# STM32F4_TFT-Proto_Adapter_FSMC.net
KiCad netlist of a schematic drawn in EAGLE
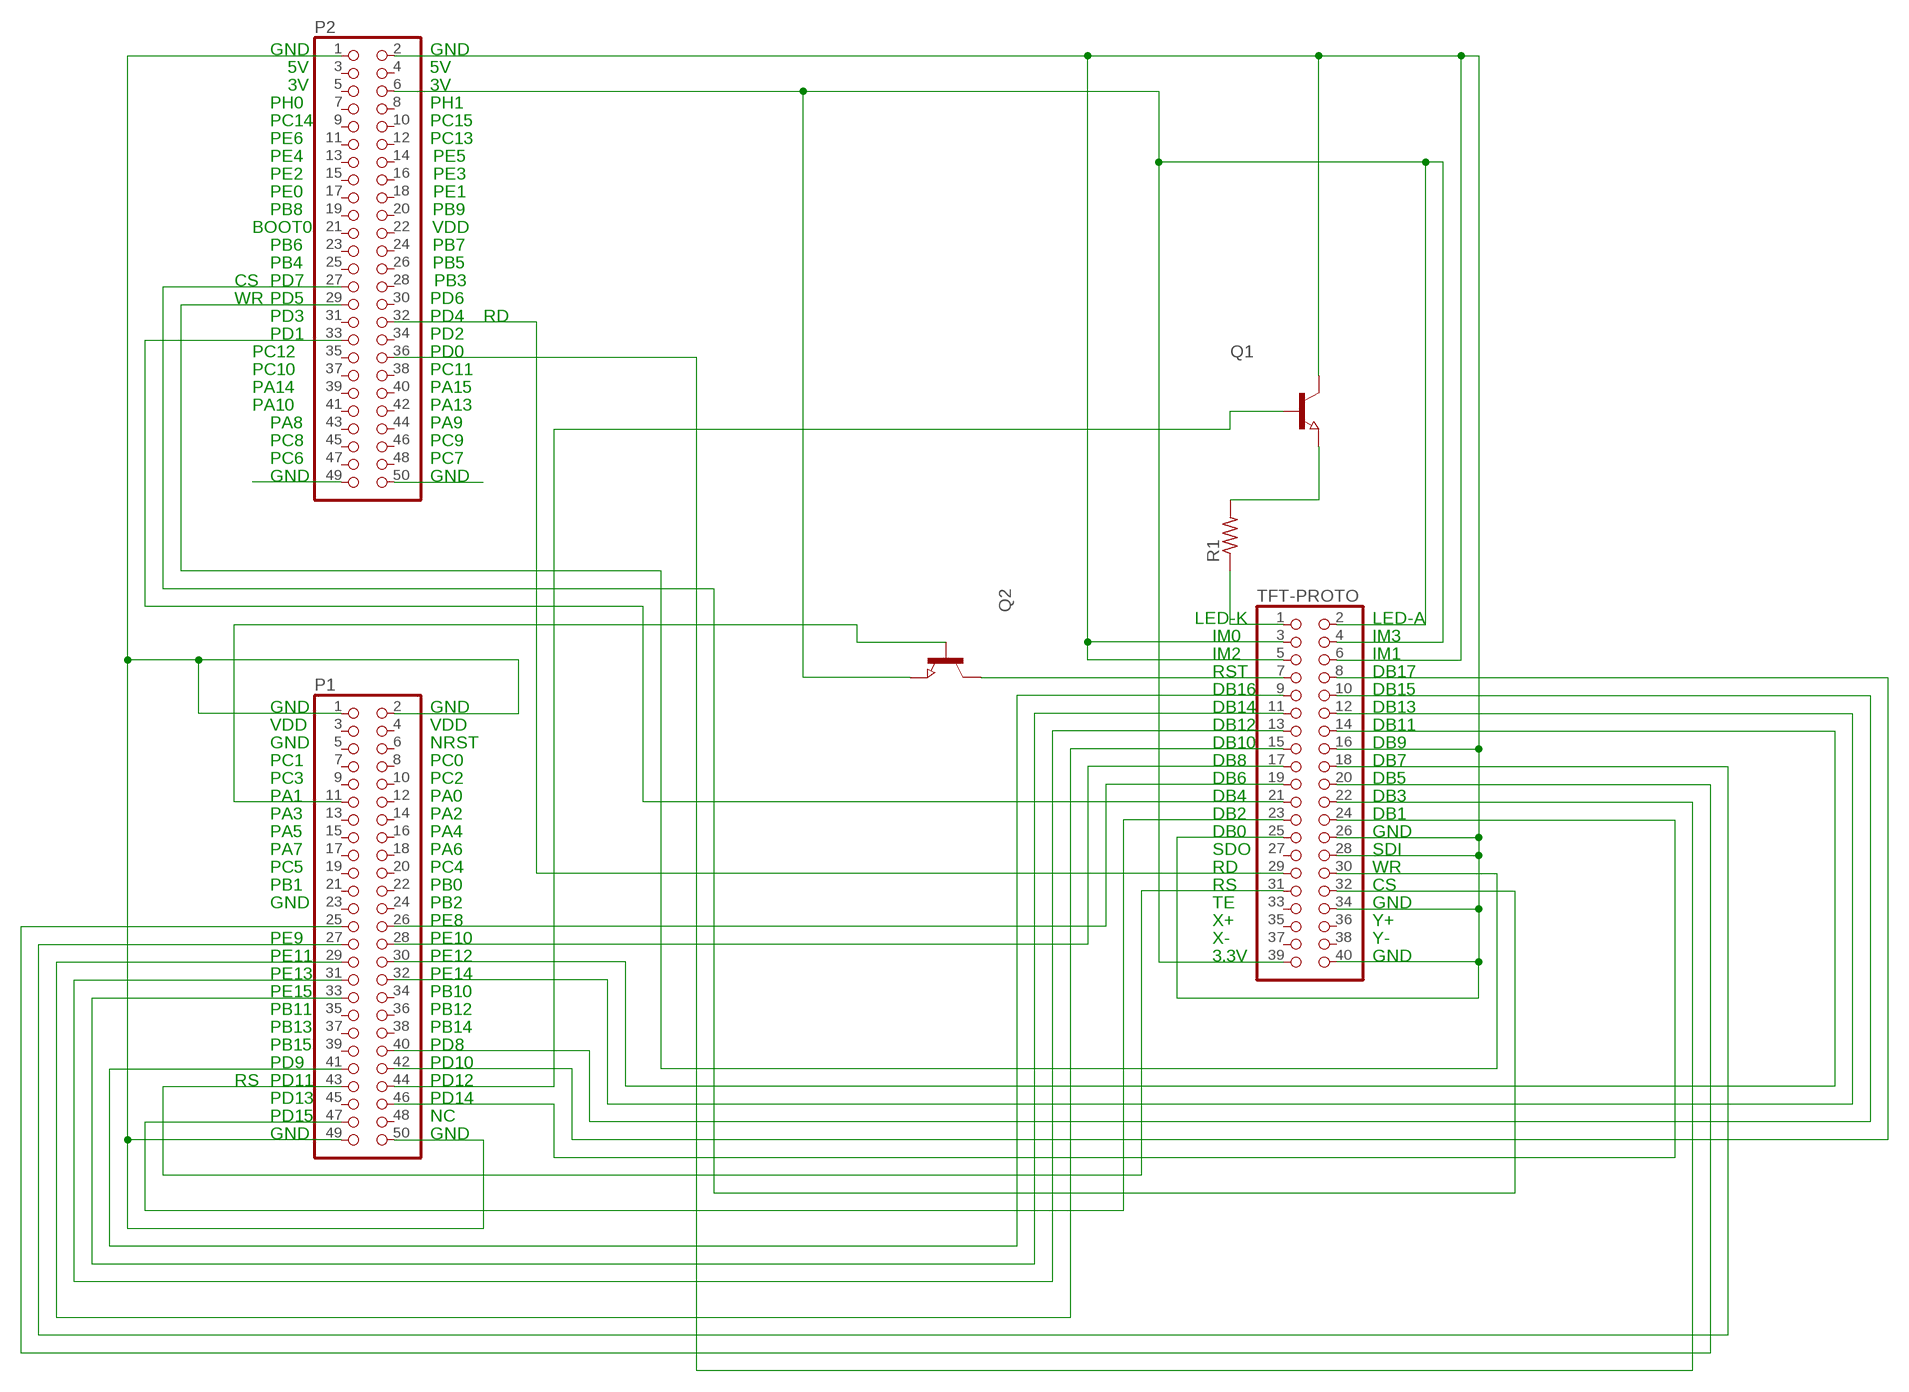
[diagram p0: schematic, sheet 1]

(export (version "E")
  (design (tool "Eeschema 10.0.6"))
  (components
    (comp (ref "P1")
      (value "PINHD-2X25")
      (footprint "eagle-import:2X25")
      (libsource (lib "eagle-import") (part "PINHD-2X25"))
    )
    (comp (ref "P2")
      (value "PINHD-2X25")
      (footprint "eagle-import:2X25")
      (libsource (lib "eagle-import") (part "PINHD-2X25"))
    )
    (comp (ref "Q1")
      (value "NPN-TRANSISTOR_SOT23")
      (footprint "eagle-import:SOT23")
      (libsource (lib "eagle-import") (part "NPN-TRANSISTOR_SOT23"))
    )
    (comp (ref "Q2")
      (value "NPN-TRANSISTOR_SOT23")
      (footprint "eagle-import:SOT23")
      (libsource (lib "eagle-import") (part "NPN-TRANSISTOR_SOT23"))
    )
    (comp (ref "R1")
      (value "R-US_R0805")
      (footprint "eagle-import:R0805")
      (libsource (lib "eagle-import") (part "R-US_R0805"))
    )
    (comp (ref "TFT-PROTO")
      (value "PINHD-2X20")
      (footprint "eagle-import:2X20")
      (libsource (lib "eagle-import") (part "PINHD-2X20"))
    )
  )
  (nets
    (net (code "1") (name "/GND") (class "Default")
      (node (ref "P1") (pin "1") (pinfunction "1_1") (pintype "passive"))
      (node (ref "P1") (pin "2") (pinfunction "2_2") (pintype "passive"))
      (node (ref "P1") (pin "49") (pinfunction "49_49") (pintype "passive"))
      (node (ref "P1") (pin "50") (pinfunction "50_50") (pintype "passive"))
      (node (ref "P2") (pin "1") (pinfunction "1_1") (pintype "passive"))
      (node (ref "P2") (pin "2") (pinfunction "2_2") (pintype "passive"))
      (node (ref "P2") (pin "49") (pinfunction "49_49") (pintype "passive"))
      (node (ref "P2") (pin "50") (pinfunction "50_50") (pintype "passive"))
      (node (ref "Q1") (pin "3") (pinfunction "C_3") (pintype "passive"))
      (node (ref "TFT-PROTO") (pin "16") (pinfunction "16_16") (pintype "passive"))
      (node (ref "TFT-PROTO") (pin "25") (pinfunction "25_25") (pintype "passive"))
      (node (ref "TFT-PROTO") (pin "26") (pinfunction "26_26") (pintype "passive"))
      (node (ref "TFT-PROTO") (pin "28") (pinfunction "28_28") (pintype "passive"))
      (node (ref "TFT-PROTO") (pin "3") (pinfunction "3_3") (pintype "passive"))
      (node (ref "TFT-PROTO") (pin "34") (pinfunction "34_34") (pintype "passive"))
      (node (ref "TFT-PROTO") (pin "40") (pinfunction "40_40") (pintype "passive"))
      (node (ref "TFT-PROTO") (pin "5") (pinfunction "5_5") (pintype "passive"))
      (node (ref "TFT-PROTO") (pin "6") (pinfunction "6_6") (pintype "passive"))
    )
    (net (code "2") (name "Net-(P1-Pad25)") (class "Default")
      (node (ref "P1") (pin "25") (pinfunction "25_25") (pintype "passive"))
      (node (ref "TFT-PROTO") (pin "20") (pinfunction "20_20") (pintype "passive"))
    )
    (net (code "3") (name "Net-(P1-Pad26)") (class "Default")
      (node (ref "P1") (pin "26") (pinfunction "26_26") (pintype "passive"))
      (node (ref "TFT-PROTO") (pin "19") (pinfunction "19_19") (pintype "passive"))
    )
    (net (code "4") (name "Net-(P1-Pad27)") (class "Default")
      (node (ref "P1") (pin "27") (pinfunction "27_27") (pintype "passive"))
      (node (ref "TFT-PROTO") (pin "18") (pinfunction "18_18") (pintype "passive"))
    )
    (net (code "5") (name "Net-(P1-Pad28)") (class "Default")
      (node (ref "P1") (pin "28") (pinfunction "28_28") (pintype "passive"))
      (node (ref "TFT-PROTO") (pin "17") (pinfunction "17_17") (pintype "passive"))
    )
    (net (code "6") (name "Net-(P1-Pad29)") (class "Default")
      (node (ref "P1") (pin "29") (pinfunction "29_29") (pintype "passive"))
      (node (ref "TFT-PROTO") (pin "15") (pinfunction "15_15") (pintype "passive"))
    )
    (net (code "7") (name "Net-(P1-Pad30)") (class "Default")
      (node (ref "P1") (pin "30") (pinfunction "30_30") (pintype "passive"))
      (node (ref "TFT-PROTO") (pin "14") (pinfunction "14_14") (pintype "passive"))
    )
    (net (code "8") (name "Net-(P1-Pad31)") (class "Default")
      (node (ref "P1") (pin "31") (pinfunction "31_31") (pintype "passive"))
      (node (ref "TFT-PROTO") (pin "13") (pinfunction "13_13") (pintype "passive"))
    )
    (net (code "9") (name "Net-(P1-Pad32)") (class "Default")
      (node (ref "P1") (pin "32") (pinfunction "32_32") (pintype "passive"))
      (node (ref "TFT-PROTO") (pin "12") (pinfunction "12_12") (pintype "passive"))
    )
    (net (code "10") (name "Net-(P1-Pad33)") (class "Default")
      (node (ref "P1") (pin "33") (pinfunction "33_33") (pintype "passive"))
      (node (ref "TFT-PROTO") (pin "11") (pinfunction "11_11") (pintype "passive"))
    )
    (net (code "11") (name "Net-(P1-Pad40)") (class "Default")
      (node (ref "P1") (pin "40") (pinfunction "40_40") (pintype "passive"))
      (node (ref "TFT-PROTO") (pin "10") (pinfunction "10_10") (pintype "passive"))
    )
    (net (code "12") (name "Net-(P1-Pad41)") (class "Default")
      (node (ref "P1") (pin "41") (pinfunction "41_41") (pintype "passive"))
      (node (ref "TFT-PROTO") (pin "9") (pinfunction "9_9") (pintype "passive"))
    )
    (net (code "13") (name "Net-(P1-Pad42)") (class "Default")
      (node (ref "P1") (pin "42") (pinfunction "42_42") (pintype "passive"))
      (node (ref "TFT-PROTO") (pin "8") (pinfunction "8_8") (pintype "passive"))
    )
    (net (code "14") (name "Net-(P1-Pad43)") (class "Default")
      (node (ref "P1") (pin "43") (pinfunction "43_43") (pintype "passive"))
      (node (ref "TFT-PROTO") (pin "31") (pinfunction "31_31") (pintype "passive"))
    )
    (net (code "15") (name "Net-(P1-Pad46)") (class "Default")
      (node (ref "P1") (pin "46") (pinfunction "46_46") (pintype "passive"))
      (node (ref "TFT-PROTO") (pin "24") (pinfunction "24_24") (pintype "passive"))
    )
    (net (code "16") (name "Net-(P1-Pad47)") (class "Default")
      (node (ref "P1") (pin "47") (pinfunction "47_47") (pintype "passive"))
      (node (ref "TFT-PROTO") (pin "23") (pinfunction "23_23") (pintype "passive"))
    )
    (net (code "17") (name "Net-(P2-Pad27)") (class "Default")
      (node (ref "P2") (pin "27") (pinfunction "27_27") (pintype "passive"))
      (node (ref "TFT-PROTO") (pin "32") (pinfunction "32_32") (pintype "passive"))
    )
    (net (code "18") (name "Net-(P2-Pad29)") (class "Default")
      (node (ref "P2") (pin "29") (pinfunction "29_29") (pintype "passive"))
      (node (ref "TFT-PROTO") (pin "30") (pinfunction "30_30") (pintype "passive"))
    )
    (net (code "19") (name "Net-(P2-Pad32)") (class "Default")
      (node (ref "P2") (pin "32") (pinfunction "32_32") (pintype "passive"))
      (node (ref "TFT-PROTO") (pin "29") (pinfunction "29_29") (pintype "passive"))
    )
    (net (code "20") (name "Net-(P2-Pad33)") (class "Default")
      (node (ref "P2") (pin "33") (pinfunction "33_33") (pintype "passive"))
      (node (ref "TFT-PROTO") (pin "21") (pinfunction "21_21") (pintype "passive"))
    )
    (net (code "21") (name "Net-(P2-Pad36)") (class "Default")
      (node (ref "P2") (pin "36") (pinfunction "36_36") (pintype "passive"))
      (node (ref "TFT-PROTO") (pin "22") (pinfunction "22_22") (pintype "passive"))
    )
    (net (code "22") (name "Net-(Q1-B)") (class "Default")
      (node (ref "P1") (pin "44") (pinfunction "44_44") (pintype "passive"))
      (node (ref "Q1") (pin "1") (pinfunction "B_1") (pintype "passive"))
    )
    (net (code "23") (name "Net-(Q1-E)") (class "Default")
      (node (ref "Q1") (pin "2") (pinfunction "E_2") (pintype "passive"))
      (node (ref "R1") (pin "2") (pinfunction "2_2") (pintype "passive"))
    )
    (net (code "24") (name "Net-(Q2-B)") (class "Default")
      (node (ref "P1") (pin "11") (pinfunction "11_11") (pintype "passive"))
      (node (ref "Q2") (pin "1") (pinfunction "B_1") (pintype "passive"))
    )
    (net (code "25") (name "Net-(Q2-C)") (class "Default")
      (node (ref "Q2") (pin "3") (pinfunction "C_3") (pintype "passive"))
      (node (ref "TFT-PROTO") (pin "7") (pinfunction "7_7") (pintype "passive"))
    )
    (net (code "26") (name "Net-(Q2-E)") (class "Default")
      (node (ref "P2") (pin "6") (pinfunction "6_6") (pintype "passive"))
      (node (ref "Q2") (pin "2") (pinfunction "E_2") (pintype "passive"))
      (node (ref "TFT-PROTO") (pin "2") (pinfunction "2_2") (pintype "passive"))
      (node (ref "TFT-PROTO") (pin "39") (pinfunction "39_39") (pintype "passive"))
      (node (ref "TFT-PROTO") (pin "4") (pinfunction "4_4") (pintype "passive"))
    )
    (net (code "27") (name "Net-(R1-Pad1)") (class "Default")
      (node (ref "R1") (pin "1") (pinfunction "1_1") (pintype "passive"))
      (node (ref "TFT-PROTO") (pin "1") (pinfunction "1_1") (pintype "passive"))
    )
    (net (code "28") (name "unconnected-(P1-Pad3)") (class "Default")
      (node (ref "P1") (pin "3") (pinfunction "3_3") (pintype "passive"))
    )
    (net (code "29") (name "unconnected-(P1-Pad4)") (class "Default")
      (node (ref "P1") (pin "4") (pinfunction "4_4") (pintype "passive"))
    )
    (net (code "30") (name "unconnected-(P1-Pad5)") (class "Default")
      (node (ref "P1") (pin "5") (pinfunction "5_5") (pintype "passive"))
    )
    (net (code "31") (name "unconnected-(P1-Pad6)") (class "Default")
      (node (ref "P1") (pin "6") (pinfunction "6_6") (pintype "passive"))
    )
    (net (code "32") (name "unconnected-(P1-Pad7)") (class "Default")
      (node (ref "P1") (pin "7") (pinfunction "7_7") (pintype "passive"))
    )
    (net (code "33") (name "unconnected-(P1-Pad8)") (class "Default")
      (node (ref "P1") (pin "8") (pinfunction "8_8") (pintype "passive"))
    )
    (net (code "34") (name "unconnected-(P1-Pad9)") (class "Default")
      (node (ref "P1") (pin "9") (pinfunction "9_9") (pintype "passive"))
    )
    (net (code "35") (name "unconnected-(P1-Pad10)") (class "Default")
      (node (ref "P1") (pin "10") (pinfunction "10_10") (pintype "passive"))
    )
    (net (code "36") (name "unconnected-(P1-Pad12)") (class "Default")
      (node (ref "P1") (pin "12") (pinfunction "12_12") (pintype "passive"))
    )
    (net (code "37") (name "unconnected-(P1-Pad13)") (class "Default")
      (node (ref "P1") (pin "13") (pinfunction "13_13") (pintype "passive"))
    )
    (net (code "38") (name "unconnected-(P1-Pad14)") (class "Default")
      (node (ref "P1") (pin "14") (pinfunction "14_14") (pintype "passive"))
    )
    (net (code "39") (name "unconnected-(P1-Pad15)") (class "Default")
      (node (ref "P1") (pin "15") (pinfunction "15_15") (pintype "passive"))
    )
    (net (code "40") (name "unconnected-(P1-Pad16)") (class "Default")
      (node (ref "P1") (pin "16") (pinfunction "16_16") (pintype "passive"))
    )
    (net (code "41") (name "unconnected-(P1-Pad17)") (class "Default")
      (node (ref "P1") (pin "17") (pinfunction "17_17") (pintype "passive"))
    )
    (net (code "42") (name "unconnected-(P1-Pad18)") (class "Default")
      (node (ref "P1") (pin "18") (pinfunction "18_18") (pintype "passive"))
    )
    (net (code "43") (name "unconnected-(P1-Pad19)") (class "Default")
      (node (ref "P1") (pin "19") (pinfunction "19_19") (pintype "passive"))
    )
    (net (code "44") (name "unconnected-(P1-Pad20)") (class "Default")
      (node (ref "P1") (pin "20") (pinfunction "20_20") (pintype "passive"))
    )
    (net (code "45") (name "unconnected-(P1-Pad21)") (class "Default")
      (node (ref "P1") (pin "21") (pinfunction "21_21") (pintype "passive"))
    )
    (net (code "46") (name "unconnected-(P1-Pad22)") (class "Default")
      (node (ref "P1") (pin "22") (pinfunction "22_22") (pintype "passive"))
    )
    (net (code "47") (name "unconnected-(P1-Pad23)") (class "Default")
      (node (ref "P1") (pin "23") (pinfunction "23_23") (pintype "passive"))
    )
    (net (code "48") (name "unconnected-(P1-Pad24)") (class "Default")
      (node (ref "P1") (pin "24") (pinfunction "24_24") (pintype "passive"))
    )
    (net (code "49") (name "unconnected-(P1-Pad34)") (class "Default")
      (node (ref "P1") (pin "34") (pinfunction "34_34") (pintype "passive"))
    )
    (net (code "50") (name "unconnected-(P1-Pad35)") (class "Default")
      (node (ref "P1") (pin "35") (pinfunction "35_35") (pintype "passive"))
    )
    (net (code "51") (name "unconnected-(P1-Pad36)") (class "Default")
      (node (ref "P1") (pin "36") (pinfunction "36_36") (pintype "passive"))
    )
    (net (code "52") (name "unconnected-(P1-Pad37)") (class "Default")
      (node (ref "P1") (pin "37") (pinfunction "37_37") (pintype "passive"))
    )
    (net (code "53") (name "unconnected-(P1-Pad38)") (class "Default")
      (node (ref "P1") (pin "38") (pinfunction "38_38") (pintype "passive"))
    )
    (net (code "54") (name "unconnected-(P1-Pad39)") (class "Default")
      (node (ref "P1") (pin "39") (pinfunction "39_39") (pintype "passive"))
    )
    (net (code "55") (name "unconnected-(P1-Pad45)") (class "Default")
      (node (ref "P1") (pin "45") (pinfunction "45_45") (pintype "passive"))
    )
    (net (code "56") (name "unconnected-(P1-Pad48)") (class "Default")
      (node (ref "P1") (pin "48") (pinfunction "48_48") (pintype "passive"))
    )
    (net (code "57") (name "unconnected-(P2-Pad3)") (class "Default")
      (node (ref "P2") (pin "3") (pinfunction "3_3") (pintype "passive"))
    )
    (net (code "58") (name "unconnected-(P2-Pad4)") (class "Default")
      (node (ref "P2") (pin "4") (pinfunction "4_4") (pintype "passive"))
    )
    (net (code "59") (name "unconnected-(P2-Pad5)") (class "Default")
      (node (ref "P2") (pin "5") (pinfunction "5_5") (pintype "passive"))
    )
    (net (code "60") (name "unconnected-(P2-Pad7)") (class "Default")
      (node (ref "P2") (pin "7") (pinfunction "7_7") (pintype "passive"))
    )
    (net (code "61") (name "unconnected-(P2-Pad8)") (class "Default")
      (node (ref "P2") (pin "8") (pinfunction "8_8") (pintype "passive"))
    )
    (net (code "62") (name "unconnected-(P2-Pad9)") (class "Default")
      (node (ref "P2") (pin "9") (pinfunction "9_9") (pintype "passive"))
    )
    (net (code "63") (name "unconnected-(P2-Pad10)") (class "Default")
      (node (ref "P2") (pin "10") (pinfunction "10_10") (pintype "passive"))
    )
    (net (code "64") (name "unconnected-(P2-Pad11)") (class "Default")
      (node (ref "P2") (pin "11") (pinfunction "11_11") (pintype "passive"))
    )
    (net (code "65") (name "unconnected-(P2-Pad12)") (class "Default")
      (node (ref "P2") (pin "12") (pinfunction "12_12") (pintype "passive"))
    )
    (net (code "66") (name "unconnected-(P2-Pad13)") (class "Default")
      (node (ref "P2") (pin "13") (pinfunction "13_13") (pintype "passive"))
    )
    (net (code "67") (name "unconnected-(P2-Pad14)") (class "Default")
      (node (ref "P2") (pin "14") (pinfunction "14_14") (pintype "passive"))
    )
    (net (code "68") (name "unconnected-(P2-Pad15)") (class "Default")
      (node (ref "P2") (pin "15") (pinfunction "15_15") (pintype "passive"))
    )
    (net (code "69") (name "unconnected-(P2-Pad16)") (class "Default")
      (node (ref "P2") (pin "16") (pinfunction "16_16") (pintype "passive"))
    )
    (net (code "70") (name "unconnected-(P2-Pad17)") (class "Default")
      (node (ref "P2") (pin "17") (pinfunction "17_17") (pintype "passive"))
    )
    (net (code "71") (name "unconnected-(P2-Pad18)") (class "Default")
      (node (ref "P2") (pin "18") (pinfunction "18_18") (pintype "passive"))
    )
    (net (code "72") (name "unconnected-(P2-Pad19)") (class "Default")
      (node (ref "P2") (pin "19") (pinfunction "19_19") (pintype "passive"))
    )
    (net (code "73") (name "unconnected-(P2-Pad20)") (class "Default")
      (node (ref "P2") (pin "20") (pinfunction "20_20") (pintype "passive"))
    )
    (net (code "74") (name "unconnected-(P2-Pad21)") (class "Default")
      (node (ref "P2") (pin "21") (pinfunction "21_21") (pintype "passive"))
    )
    (net (code "75") (name "unconnected-(P2-Pad22)") (class "Default")
      (node (ref "P2") (pin "22") (pinfunction "22_22") (pintype "passive"))
    )
    (net (code "76") (name "unconnected-(P2-Pad23)") (class "Default")
      (node (ref "P2") (pin "23") (pinfunction "23_23") (pintype "passive"))
    )
    (net (code "77") (name "unconnected-(P2-Pad24)") (class "Default")
      (node (ref "P2") (pin "24") (pinfunction "24_24") (pintype "passive"))
    )
    (net (code "78") (name "unconnected-(P2-Pad25)") (class "Default")
      (node (ref "P2") (pin "25") (pinfunction "25_25") (pintype "passive"))
    )
    (net (code "79") (name "unconnected-(P2-Pad26)") (class "Default")
      (node (ref "P2") (pin "26") (pinfunction "26_26") (pintype "passive"))
    )
    (net (code "80") (name "unconnected-(P2-Pad28)") (class "Default")
      (node (ref "P2") (pin "28") (pinfunction "28_28") (pintype "passive"))
    )
    (net (code "81") (name "unconnected-(P2-Pad30)") (class "Default")
      (node (ref "P2") (pin "30") (pinfunction "30_30") (pintype "passive"))
    )
    (net (code "82") (name "unconnected-(P2-Pad31)") (class "Default")
      (node (ref "P2") (pin "31") (pinfunction "31_31") (pintype "passive"))
    )
    (net (code "83") (name "unconnected-(P2-Pad34)") (class "Default")
      (node (ref "P2") (pin "34") (pinfunction "34_34") (pintype "passive"))
    )
    (net (code "84") (name "unconnected-(P2-Pad35)") (class "Default")
      (node (ref "P2") (pin "35") (pinfunction "35_35") (pintype "passive"))
    )
    (net (code "85") (name "unconnected-(P2-Pad37)") (class "Default")
      (node (ref "P2") (pin "37") (pinfunction "37_37") (pintype "passive"))
    )
    (net (code "86") (name "unconnected-(P2-Pad38)") (class "Default")
      (node (ref "P2") (pin "38") (pinfunction "38_38") (pintype "passive"))
    )
    (net (code "87") (name "unconnected-(P2-Pad39)") (class "Default")
      (node (ref "P2") (pin "39") (pinfunction "39_39") (pintype "passive"))
    )
    (net (code "88") (name "unconnected-(P2-Pad40)") (class "Default")
      (node (ref "P2") (pin "40") (pinfunction "40_40") (pintype "passive"))
    )
    (net (code "89") (name "unconnected-(P2-Pad41)") (class "Default")
      (node (ref "P2") (pin "41") (pinfunction "41_41") (pintype "passive"))
    )
    (net (code "90") (name "unconnected-(P2-Pad42)") (class "Default")
      (node (ref "P2") (pin "42") (pinfunction "42_42") (pintype "passive"))
    )
    (net (code "91") (name "unconnected-(P2-Pad43)") (class "Default")
      (node (ref "P2") (pin "43") (pinfunction "43_43") (pintype "passive"))
    )
    (net (code "92") (name "unconnected-(P2-Pad44)") (class "Default")
      (node (ref "P2") (pin "44") (pinfunction "44_44") (pintype "passive"))
    )
    (net (code "93") (name "unconnected-(P2-Pad45)") (class "Default")
      (node (ref "P2") (pin "45") (pinfunction "45_45") (pintype "passive"))
    )
    (net (code "94") (name "unconnected-(P2-Pad46)") (class "Default")
      (node (ref "P2") (pin "46") (pinfunction "46_46") (pintype "passive"))
    )
    (net (code "95") (name "unconnected-(P2-Pad47)") (class "Default")
      (node (ref "P2") (pin "47") (pinfunction "47_47") (pintype "passive"))
    )
    (net (code "96") (name "unconnected-(P2-Pad48)") (class "Default")
      (node (ref "P2") (pin "48") (pinfunction "48_48") (pintype "passive"))
    )
    (net (code "97") (name "unconnected-(TFT-PROTO-Pad27)") (class "Default")
      (node (ref "TFT-PROTO") (pin "27") (pinfunction "27_27") (pintype "passive"))
    )
    (net (code "98") (name "unconnected-(TFT-PROTO-Pad33)") (class "Default")
      (node (ref "TFT-PROTO") (pin "33") (pinfunction "33_33") (pintype "passive"))
    )
    (net (code "99") (name "unconnected-(TFT-PROTO-Pad35)") (class "Default")
      (node (ref "TFT-PROTO") (pin "35") (pinfunction "35_35") (pintype "passive"))
    )
    (net (code "100") (name "unconnected-(TFT-PROTO-Pad36)") (class "Default")
      (node (ref "TFT-PROTO") (pin "36") (pinfunction "36_36") (pintype "passive"))
    )
    (net (code "101") (name "unconnected-(TFT-PROTO-Pad37)") (class "Default")
      (node (ref "TFT-PROTO") (pin "37") (pinfunction "37_37") (pintype "passive"))
    )
    (net (code "102") (name "unconnected-(TFT-PROTO-Pad38)") (class "Default")
      (node (ref "TFT-PROTO") (pin "38") (pinfunction "38_38") (pintype "passive"))
    )
  )
)
